# timer2.net
KiCad netlist of a schematic drawn in EAGLE
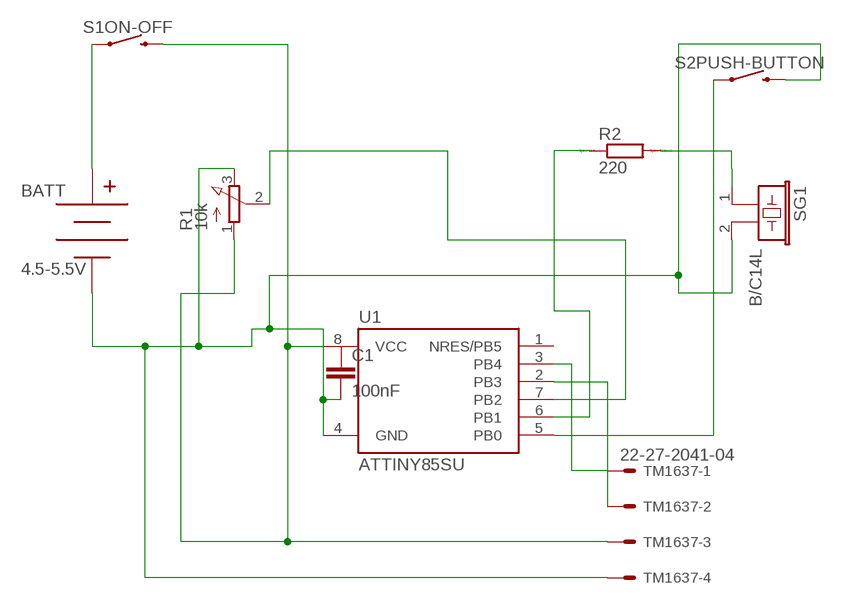
[diagram p0: schematic, sheet 1]

(export (version "E")
  (design (tool "Eeschema 10.0.6"))
  (components
    (comp (ref "BATT")
      (value "4.5-5.5V")
      (footprint "eagle-import:BC9VPC")
      (libsource (lib "eagle-import") (part "BC9VPC"))
    )
    (comp (ref "C1")
      (value "100nF")
      (footprint "eagle-import:C025-024X044")
      (libsource (lib "eagle-import") (part "C-EU025-024X044"))
    )
    (comp (ref "R1")
      (value "10k")
      (footprint "eagle-import:3RP_1610N")
      (libsource (lib "eagle-import") (part "3RP/1610N"))
    )
    (comp (ref "R2")
      (value "220")
      (footprint "eagle-import:0204_7")
      (libsource (lib "eagle-import") (part "R0204/7"))
    )
    (comp (ref "S1ON-OFF")
      (value "MOMENTARY-SWITCH-SPST-PTH-6.0MM")
      (footprint "eagle-import:TACTILE_SWITCH_PTH_6.0MM")
      (libsource (lib "eagle-import") (part "MOMENTARY-SWITCH-SPST-PTH-6.0MM"))
    )
    (comp (ref "S2PUSH-BUTTON")
      (value "MOMENTARY-SWITCH-SPST-PTH-6.0MM")
      (footprint "eagle-import:TACTILE_SWITCH_PTH_6.0MM")
      (libsource (lib "eagle-import") (part "MOMENTARY-SWITCH-SPST-PTH-6.0MM"))
    )
    (comp (ref "SG1")
      (value "B/C14L")
      (footprint "eagle-import:B_C14L")
      (libsource (lib "eagle-import") (part "B/C14L"))
    )
    (comp (ref "TM1637")
      (value "22-27-2041-04")
      (footprint "eagle-import:6410-04")
      (fields (field (name "MF") "MOLEX"))
      (libsource (lib "eagle-import") (part "22-?-0427-2041"))
    )
    (comp (ref "U1")
      (value "ATTINY85SU")
      (footprint "eagle-import:ATTINY85")
      (libsource (lib "eagle-import") (part "ATTINY85SU"))
    )
  )
  (nets
    (net (code "1") (name "Net-(BATT-PadV+)") (class "Default")
      (node (ref "BATT") (pin "V+") (pinfunction "V+_V+") (pintype "bidirectional"))
      (node (ref "S1ON-OFF") (pin "1") (pinfunction "1_1") (pintype "passive"))
    )
    (net (code "2") (name "Net-(R1-A)") (class "Default")
      (node (ref "R1") (pin "1") (pinfunction "A_1") (pintype "passive"))
      (node (ref "S1ON-OFF") (pin "3") (pinfunction "2_3") (pintype "passive"))
      (node (ref "TM1637") (pin "3") (pinfunction "S_3") (pintype "passive"))
      (node (ref "U1") (pin "8") (pinfunction "VCC_8") (pintype "power_in"))
    )
    (net (code "3") (name "Net-(R1-E)") (class "Default")
      (node (ref "BATT") (pin "V-") (pinfunction "V-_V-") (pintype "bidirectional"))
      (node (ref "C1") (pin "2") (pinfunction "2_2") (pintype "passive"))
      (node (ref "R1") (pin "3") (pinfunction "E_3") (pintype "passive"))
      (node (ref "S2PUSH-BUTTON") (pin "3") (pinfunction "2_3") (pintype "passive"))
      (node (ref "SG1") (pin "2") (pinfunction "2_2") (pintype "passive"))
      (node (ref "TM1637") (pin "4") (pinfunction "S_4") (pintype "passive"))
      (node (ref "U1") (pin "4") (pinfunction "GND_4") (pintype "power_in"))
    )
    (net (code "4") (name "Net-(R1-S)") (class "Default")
      (node (ref "R1") (pin "2") (pinfunction "S_2") (pintype "passive"))
      (node (ref "U1") (pin "7") (pinfunction "PB2_7") (pintype "bidirectional"))
    )
    (net (code "5") (name "Net-(R2-Pad2)") (class "Default")
      (node (ref "R2") (pin "2") (pinfunction "2_2") (pintype "passive"))
      (node (ref "SG1") (pin "1") (pinfunction "1_1") (pintype "passive"))
    )
    (net (code "6") (name "Net-(TM1637A-S)") (class "Default")
      (node (ref "TM1637") (pin "1") (pinfunction "S_1") (pintype "passive"))
      (node (ref "U1") (pin "3") (pinfunction "PB4_3") (pintype "bidirectional"))
    )
    (net (code "7") (name "Net-(TM1637B-S)") (class "Default")
      (node (ref "TM1637") (pin "2") (pinfunction "S_2") (pintype "passive"))
      (node (ref "U1") (pin "2") (pinfunction "PB3_2") (pintype "bidirectional"))
    )
    (net (code "8") (name "Net-(U1-PB0)") (class "Default")
      (node (ref "S2PUSH-BUTTON") (pin "1") (pinfunction "1_1") (pintype "passive"))
      (node (ref "U1") (pin "5") (pinfunction "PB0_5") (pintype "bidirectional"))
    )
    (net (code "9") (name "Net-(U1-PB1)") (class "Default")
      (node (ref "R2") (pin "1") (pinfunction "1_1") (pintype "passive"))
      (node (ref "U1") (pin "6") (pinfunction "PB1_6") (pintype "bidirectional"))
    )
    (net (code "10") (name "unconnected-(C1-Pad1)") (class "Default")
      (node (ref "C1") (pin "1") (pinfunction "1_1") (pintype "passive"))
    )
    (net (code "11") (name "unconnected-(U1-NRES{slash}PB5-Pad1)") (class "Default")
      (node (ref "U1") (pin "1") (pinfunction "NRES/PB5_1") (pintype "bidirectional"))
    )
  )
)
